# LED_Circuit.net
KiCad netlist of a schematic drawn in Altium Designer
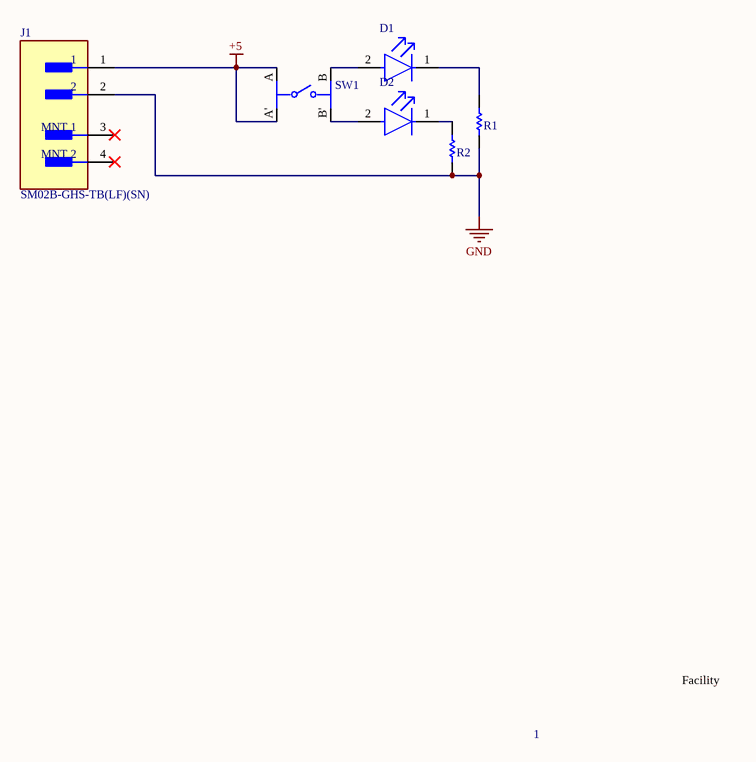
[diagram p0: LED_Circuit.SchDoc]

(export (version "E")
  (design (tool "Eeschema 10.0.6"))
  (components
    (comp (ref "D1")
      (value "HSMG-C150")
      (footprint "FP-HSMG-C150-MFG")
      (description "Surface Mount Chip LEDs")
      (fields (field (name "MANUFACTURER") "Broadcom"))
      (libsource (lib "Altium Content Vault") (part "8706943c75ba83719d021d2fdc84c58"))
    )
    (comp (ref "D2")
      (value "HSMG-C150")
      (footprint "FP-HSMG-C150-MFG")
      (description "Surface Mount Chip LEDs")
      (fields (field (name "MANUFACTURER") "Broadcom"))
      (libsource (lib "Altium Content Vault") (part "8706943c75ba83719d021d2fdc84c58"))
    )
    (comp (ref "J1")
      (value "SM02B-GHS-TB(LF)(SN)")
      (footprint "FP-SM02B-GHS-TB_LF_SN-MFG")
      (description "CONN HEADER SMD R/A 2POS 1.25MM")
      (libsource (lib "Altium Content Vault") (part "56ec3178a87b3978bdc1b3682cd516a"))
    )
    (comp (ref "R1")
      (value "ERJ8CWFR018V")
      (footprint "RESC3216X70X50NL05T20")
      (fields (field (name "MANUFACTURER") "Panasonic"))
      (libsource (lib "Altium Content Vault") (part "RES"))
    )
    (comp (ref "R2")
      (value "ERJ8CWFR018V")
      (footprint "RESC3216X70X50NL05T20")
      (fields (field (name "MANUFACTURER") "Panasonic"))
      (libsource (lib "Altium Content Vault") (part "RES"))
    )
    (comp (ref "SW1")
      (value "EVQ-Q2P03W")
      (footprint "FP-EVQ-Q2P03W-MFG")
      (description "SWITCH TACTILE SPST-NO 0.02A 15V")
      (libsource (lib "Altium Content Vault") (part "9677229990528492022b31d4503349f"))
    )
  )
  (nets
    (net (code "1") (name "+5") (class "Default")
      (node (ref "J1") (pin "1") (pinfunction "1_1") (pintype "passive"))
      (node (ref "SW1") (pin "A") (pinfunction "A_A") (pintype "passive"))
      (node (ref "SW1") (pin "A'") (pinfunction "A'_A'") (pintype "passive"))
    )
    (net (code "2") (name "GND") (class "Default")
      (node (ref "J1") (pin "2") (pinfunction "2_2") (pintype "passive"))
      (node (ref "R1") (pin "1") (pinfunction "1_1") (pintype "passive"))
      (node (ref "R2") (pin "1") (pinfunction "1_1") (pintype "passive"))
    )
    (net (code "3") (name "Net-(D1-A)") (class "Default")
      (node (ref "D1") (pin "2") (pinfunction "A_2") (pintype "passive"))
      (node (ref "SW1") (pin "B") (pinfunction "B_B") (pintype "passive"))
    )
    (net (code "4") (name "Net-(D1-C)") (class "Default")
      (node (ref "D1") (pin "1") (pinfunction "C_1") (pintype "passive"))
      (node (ref "R1") (pin "2") (pinfunction "2_2") (pintype "passive"))
    )
    (net (code "5") (name "Net-(D2-A)") (class "Default")
      (node (ref "D2") (pin "2") (pinfunction "A_2") (pintype "passive"))
      (node (ref "SW1") (pin "B'") (pinfunction "B'_B'") (pintype "passive"))
    )
    (net (code "6") (name "Net-(D2-C)") (class "Default")
      (node (ref "D2") (pin "1") (pinfunction "C_1") (pintype "passive"))
      (node (ref "R2") (pin "2") (pinfunction "2_2") (pintype "passive"))
    )
    (net (code "7") (name "unconnected-(J1-MNT_1-Pad3)") (class "Default")
      (node (ref "J1") (pin "3") (pinfunction "MNT_1_3") (pintype "passive+no_connect"))
    )
    (net (code "8") (name "unconnected-(J1-MNT_2-Pad4)") (class "Default")
      (node (ref "J1") (pin "4") (pinfunction "MNT_2_4") (pintype "passive+no_connect"))
    )
  )
)
